# EndStops.net
KiCad netlist of a schematic drawn in Altium Designer
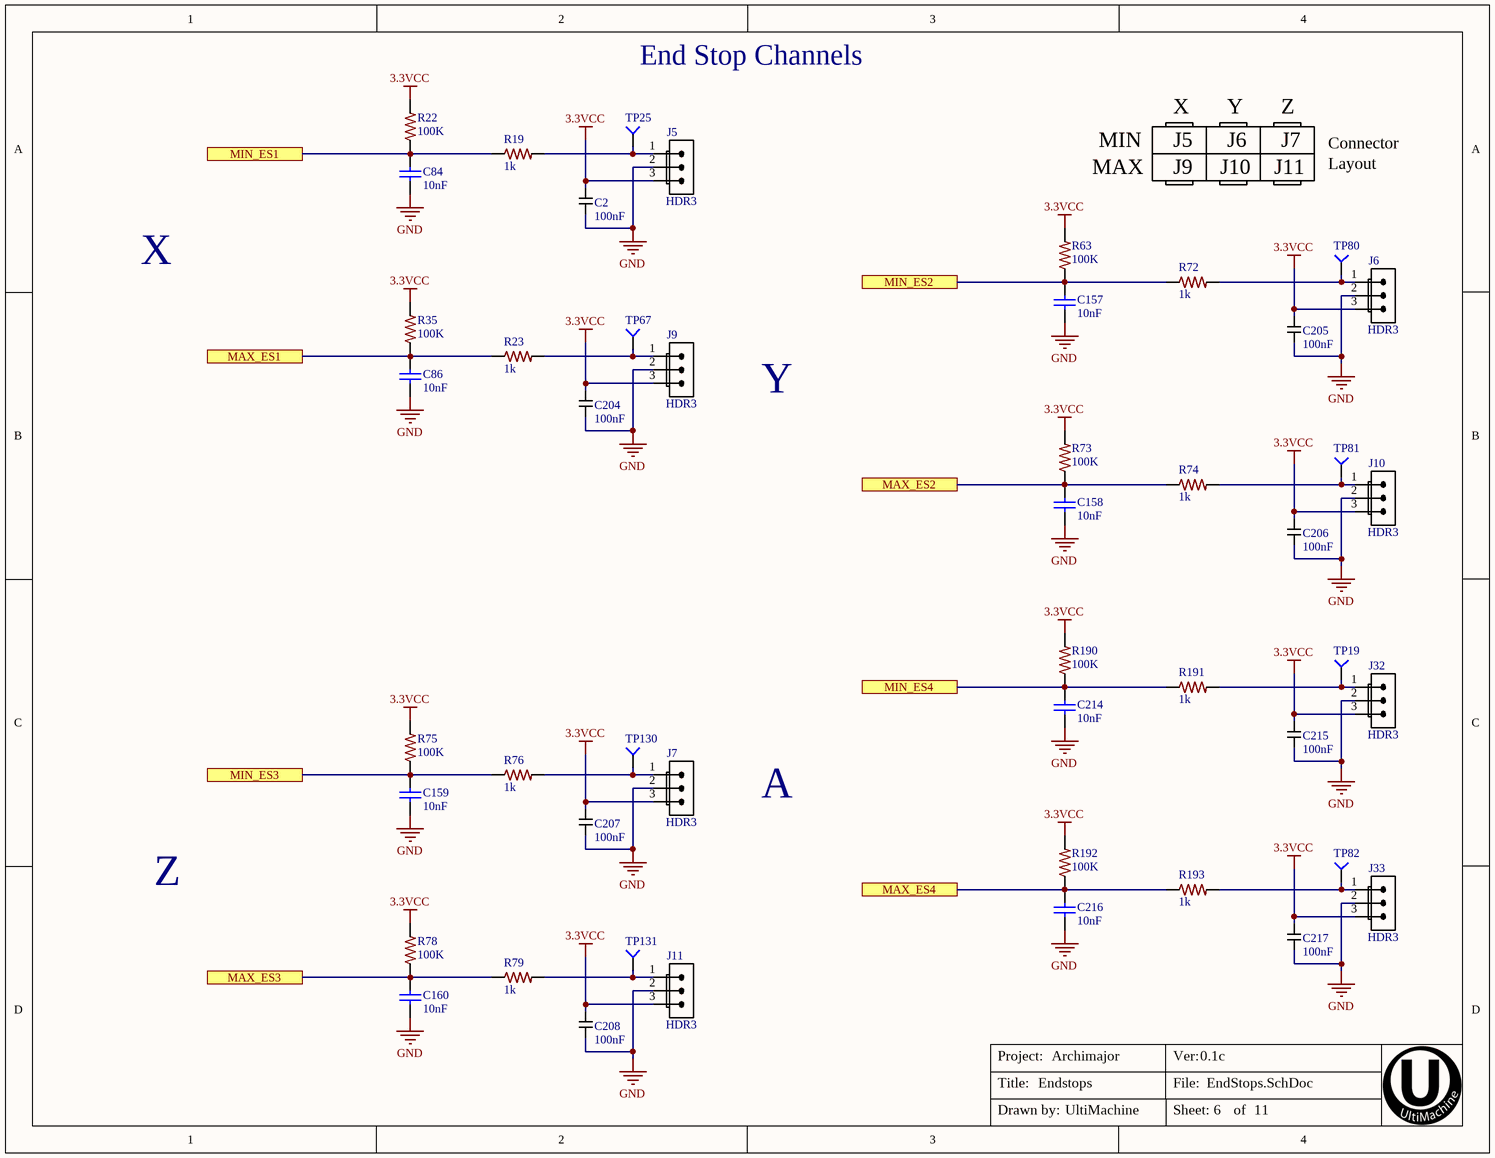
[diagram p0: EndStops.SchDoc]

(export (version "E")
  (design (tool "Eeschema 10.0.6"))
  (components
    (comp (ref "C2")
      (value "100nF")
      (footprint "C0201 Large Pads")
      (description "CAP CER 0.1UF 6.3V 10% X5R 0201")
      (fields (field (name "PART") "CL03A104KQ3NNNC") (field (name "MANUFACTURER") "Samsung"))
      (libsource (lib "Capacitors") (part "100nF 6.3V X5R 0201"))
    )
    (comp (ref "C84")
      (value "10nF")
      (footprint "C0402")
      (description "CAP CER 10nF 50V X7R 0402")
      (fields (field (name "TOLERANCE") "5%") (field (name "MANUFACTURER") "Murata"))
      (libsource (lib "Tigershark3D") (part "GRM155R71H103JA88D"))
    )
    (comp (ref "C86")
      (value "10nF")
      (footprint "C0402")
      (description "CAP CER 10nF 50V X7R 0402")
      (fields (field (name "TOLERANCE") "5%") (field (name "MANUFACTURER") "Murata"))
      (libsource (lib "Tigershark3D") (part "GRM155R71H103JA88D"))
    )
    (comp (ref "C157")
      (value "10nF")
      (footprint "C0402")
      (description "CAP CER 10nF 50V X7R 0402")
      (fields (field (name "TOLERANCE") "5%") (field (name "MANUFACTURER") "Murata"))
      (libsource (lib "Tigershark3D") (part "GRM155R71H103JA88D"))
    )
    (comp (ref "C158")
      (value "10nF")
      (footprint "C0402")
      (description "CAP CER 10nF 50V X7R 0402")
      (fields (field (name "TOLERANCE") "5%") (field (name "MANUFACTURER") "Murata"))
      (libsource (lib "Tigershark3D") (part "GRM155R71H103JA88D"))
    )
    (comp (ref "C159")
      (value "10nF")
      (footprint "C0402")
      (description "CAP CER 10nF 50V X7R 0402")
      (fields (field (name "TOLERANCE") "5%") (field (name "MANUFACTURER") "Murata"))
      (libsource (lib "Tigershark3D") (part "GRM155R71H103JA88D"))
    )
    (comp (ref "C160")
      (value "10nF")
      (footprint "C0402")
      (description "CAP CER 10nF 50V X7R 0402")
      (fields (field (name "TOLERANCE") "5%") (field (name "MANUFACTURER") "Murata"))
      (libsource (lib "Tigershark3D") (part "GRM155R71H103JA88D"))
    )
    (comp (ref "C204")
      (value "100nF")
      (footprint "C0201 Large Pads")
      (description "CAP CER 0.1UF 6.3V 10% X5R 0201")
      (fields (field (name "PART") "CL03A104KQ3NNNC") (field (name "MANUFACTURER") "Samsung"))
      (libsource (lib "Capacitors") (part "100nF 6.3V X5R 0201"))
    )
    (comp (ref "C205")
      (value "100nF")
      (footprint "C0201 Large Pads")
      (description "CAP CER 0.1UF 6.3V 10% X5R 0201")
      (fields (field (name "PART") "CL03A104KQ3NNNC") (field (name "MANUFACTURER") "Samsung"))
      (libsource (lib "Capacitors") (part "100nF 6.3V X5R 0201"))
    )
    (comp (ref "C206")
      (value "100nF")
      (footprint "C0201 Large Pads")
      (description "CAP CER 0.1UF 6.3V 10% X5R 0201")
      (fields (field (name "PART") "CL03A104KQ3NNNC") (field (name "MANUFACTURER") "Samsung"))
      (libsource (lib "Capacitors") (part "100nF 6.3V X5R 0201"))
    )
    (comp (ref "C207")
      (value "100nF")
      (footprint "C0201 Large Pads")
      (description "CAP CER 0.1UF 6.3V 10% X5R 0201")
      (fields (field (name "PART") "CL03A104KQ3NNNC") (field (name "MANUFACTURER") "Samsung"))
      (libsource (lib "Capacitors") (part "100nF 6.3V X5R 0201"))
    )
    (comp (ref "C208")
      (value "100nF")
      (footprint "C0201 Large Pads")
      (description "CAP CER 0.1UF 6.3V 10% X5R 0201")
      (fields (field (name "PART") "CL03A104KQ3NNNC") (field (name "MANUFACTURER") "Samsung"))
      (libsource (lib "Capacitors") (part "100nF 6.3V X5R 0201"))
    )
    (comp (ref "C214")
      (value "10nF")
      (footprint "C0402")
      (description "CAP CER 10nF 50V X7R 0402")
      (fields (field (name "TOLERANCE") "5%") (field (name "MANUFACTURER") "Murata"))
      (libsource (lib "Tigershark3D") (part "GRM155R71H103JA88D"))
    )
    (comp (ref "C215")
      (value "100nF")
      (footprint "C0201 Large Pads")
      (description "CAP CER 0.1UF 6.3V 10% X5R 0201")
      (fields (field (name "PART") "CL03A104KQ3NNNC") (field (name "MANUFACTURER") "Samsung"))
      (libsource (lib "Capacitors") (part "100nF 6.3V X5R 0201"))
    )
    (comp (ref "C216")
      (value "10nF")
      (footprint "C0402")
      (description "CAP CER 10nF 50V X7R 0402")
      (fields (field (name "TOLERANCE") "5%") (field (name "MANUFACTURER") "Murata"))
      (libsource (lib "Tigershark3D") (part "GRM155R71H103JA88D"))
    )
    (comp (ref "C217")
      (value "100nF")
      (footprint "C0201 Large Pads")
      (description "CAP CER 0.1UF 6.3V 10% X5R 0201")
      (fields (field (name "PART") "CL03A104KQ3NNNC") (field (name "MANUFACTURER") "Samsung"))
      (libsource (lib "Capacitors") (part "100nF 6.3V X5R 0201"))
    )
    (comp (ref "J5")
      (value "HDR3")
      (footprint "70543-02 PIN-IN-PASTE")
      (description "3 Positions Header, Shrouded Connector 0.100\" (2.54mm) Through Hole Gold - Pin in Paste")
      (fields (field (name "MANUFACTURER") "Molex") (field (name "PART") "0705430002"))
      (libsource (lib "Connectors") (part "CONN 3POS VERT 0.1{dblquote} SHRD LOCKING PIP"))
    )
    (comp (ref "J6")
      (value "HDR3")
      (footprint "70543-02 PIN-IN-PASTE")
      (description "3 Positions Header, Shrouded Connector 0.100\" (2.54mm) Through Hole Gold - Pin in Paste")
      (fields (field (name "MANUFACTURER") "Molex") (field (name "PART") "0705430002"))
      (libsource (lib "Connectors") (part "CONN 3POS VERT 0.1{dblquote} SHRD LOCKING PIP"))
    )
    (comp (ref "J7")
      (value "HDR3")
      (footprint "70543-02 PIN-IN-PASTE")
      (description "3 Positions Header, Shrouded Connector 0.100\" (2.54mm) Through Hole Gold - Pin in Paste")
      (fields (field (name "MANUFACTURER") "Molex") (field (name "PART") "0705430002"))
      (libsource (lib "Connectors") (part "CONN 3POS VERT 0.1{dblquote} SHRD LOCKING PIP"))
    )
    (comp (ref "J9")
      (value "HDR3")
      (footprint "70543-02 PIN-IN-PASTE")
      (description "3 Positions Header, Shrouded Connector 0.100\" (2.54mm) Through Hole Gold - Pin in Paste")
      (fields (field (name "MANUFACTURER") "Molex") (field (name "PART") "0705430002"))
      (libsource (lib "Connectors") (part "CONN 3POS VERT 0.1{dblquote} SHRD LOCKING PIP"))
    )
    (comp (ref "J10")
      (value "HDR3")
      (footprint "70543-02 PIN-IN-PASTE")
      (description "3 Positions Header, Shrouded Connector 0.100\" (2.54mm) Through Hole Gold - Pin in Paste")
      (fields (field (name "MANUFACTURER") "Molex") (field (name "PART") "0705430002"))
      (libsource (lib "Connectors") (part "CONN 3POS VERT 0.1{dblquote} SHRD LOCKING PIP"))
    )
    (comp (ref "J11")
      (value "HDR3")
      (footprint "70543-02 PIN-IN-PASTE")
      (description "3 Positions Header, Shrouded Connector 0.100\" (2.54mm) Through Hole Gold - Pin in Paste")
      (fields (field (name "MANUFACTURER") "Molex") (field (name "PART") "0705430002"))
      (libsource (lib "Connectors") (part "CONN 3POS VERT 0.1{dblquote} SHRD LOCKING PIP"))
    )
    (comp (ref "J32")
      (value "HDR3")
      (footprint "70543-02 PIN-IN-PASTE")
      (description "3 Positions Header, Shrouded Connector 0.100\" (2.54mm) Through Hole Gold - Pin in Paste")
      (fields (field (name "MANUFACTURER") "Molex") (field (name "PART") "0705430002"))
      (libsource (lib "Connectors") (part "CONN 3POS VERT 0.1{dblquote} SHRD LOCKING PIP"))
    )
    (comp (ref "J33")
      (value "HDR3")
      (footprint "70543-02 PIN-IN-PASTE")
      (description "3 Positions Header, Shrouded Connector 0.100\" (2.54mm) Through Hole Gold - Pin in Paste")
      (fields (field (name "MANUFACTURER") "Molex") (field (name "PART") "0705430002"))
      (libsource (lib "Connectors") (part "CONN 3POS VERT 0.1{dblquote} SHRD LOCKING PIP"))
    )
    (comp (ref "R19")
      (value "1k")
      (footprint "R0402")
      (description "RES 0402 1k 63mW 1%")
      (fields (field (name "MANUFACTURER") "Yageo") (field (name "PART") "RC0402FR-071KL"))
      (libsource (lib "3Delight") (part "RK73H1ETTP1001F"))
    )
    (comp (ref "R22")
      (value "100K")
      (footprint "R0402")
      (description "RES SMD 100K OHM 1% 1/16W 0402")
      (fields (field (name "MANUFACTURER") "Samsung") (field (name "PART") "RC1005F104CS"))
      (libsource (lib "Tigershark3D") (part "RC1005F104CS"))
    )
    (comp (ref "R23")
      (value "1k")
      (footprint "R0402")
      (description "RES 0402 1k 63mW 1%")
      (fields (field (name "MANUFACTURER") "Yageo") (field (name "PART") "RC0402FR-071KL"))
      (libsource (lib "3Delight") (part "RK73H1ETTP1001F"))
    )
    (comp (ref "R35")
      (value "100K")
      (footprint "R0402")
      (description "RES SMD 100K OHM 1% 1/16W 0402")
      (fields (field (name "MANUFACTURER") "Samsung") (field (name "PART") "RC1005F104CS"))
      (libsource (lib "Tigershark3D") (part "RC1005F104CS"))
    )
    (comp (ref "R63")
      (value "100K")
      (footprint "R0402")
      (description "RES SMD 100K OHM 1% 1/16W 0402")
      (fields (field (name "MANUFACTURER") "Samsung") (field (name "PART") "RC1005F104CS"))
      (libsource (lib "Tigershark3D") (part "RC1005F104CS"))
    )
    (comp (ref "R72")
      (value "1k")
      (footprint "R0402")
      (description "RES 0402 1k 63mW 1%")
      (fields (field (name "MANUFACTURER") "Yageo") (field (name "PART") "RC0402FR-071KL"))
      (libsource (lib "3Delight") (part "RK73H1ETTP1001F"))
    )
    (comp (ref "R73")
      (value "100K")
      (footprint "R0402")
      (description "RES SMD 100K OHM 1% 1/16W 0402")
      (fields (field (name "MANUFACTURER") "Samsung") (field (name "PART") "RC1005F104CS"))
      (libsource (lib "Tigershark3D") (part "RC1005F104CS"))
    )
    (comp (ref "R74")
      (value "1k")
      (footprint "R0402")
      (description "RES 0402 1k 63mW 1%")
      (fields (field (name "MANUFACTURER") "Yageo") (field (name "PART") "RC0402FR-071KL"))
      (libsource (lib "3Delight") (part "RK73H1ETTP1001F"))
    )
    (comp (ref "R75")
      (value "100K")
      (footprint "R0402")
      (description "RES SMD 100K OHM 1% 1/16W 0402")
      (fields (field (name "MANUFACTURER") "Samsung") (field (name "PART") "RC1005F104CS"))
      (libsource (lib "Tigershark3D") (part "RC1005F104CS"))
    )
    (comp (ref "R76")
      (value "1k")
      (footprint "R0402")
      (description "RES 0402 1k 63mW 1%")
      (fields (field (name "MANUFACTURER") "Yageo") (field (name "PART") "RC0402FR-071KL"))
      (libsource (lib "3Delight") (part "RK73H1ETTP1001F"))
    )
    (comp (ref "R78")
      (value "100K")
      (footprint "R0402")
      (description "RES SMD 100K OHM 1% 1/16W 0402")
      (fields (field (name "MANUFACTURER") "Samsung") (field (name "PART") "RC1005F104CS"))
      (libsource (lib "Tigershark3D") (part "RC1005F104CS"))
    )
    (comp (ref "R79")
      (value "1k")
      (footprint "R0402")
      (description "RES 0402 1k 63mW 1%")
      (fields (field (name "MANUFACTURER") "Yageo") (field (name "PART") "RC0402FR-071KL"))
      (libsource (lib "3Delight") (part "RK73H1ETTP1001F"))
    )
    (comp (ref "R190")
      (value "100K")
      (footprint "R0402")
      (description "RES SMD 100K OHM 1% 1/16W 0402")
      (fields (field (name "MANUFACTURER") "Samsung") (field (name "PART") "RC1005F104CS"))
      (libsource (lib "Tigershark3D") (part "RC1005F104CS"))
    )
    (comp (ref "R191")
      (value "1k")
      (footprint "R0402")
      (description "RES 0402 1k 63mW 1%")
      (fields (field (name "MANUFACTURER") "Yageo") (field (name "PART") "RC0402FR-071KL"))
      (libsource (lib "3Delight") (part "RK73H1ETTP1001F"))
    )
    (comp (ref "R192")
      (value "100K")
      (footprint "R0402")
      (description "RES SMD 100K OHM 1% 1/16W 0402")
      (fields (field (name "MANUFACTURER") "Samsung") (field (name "PART") "RC1005F104CS"))
      (libsource (lib "Tigershark3D") (part "RC1005F104CS"))
    )
    (comp (ref "R193")
      (value "1k")
      (footprint "R0402")
      (description "RES 0402 1k 63mW 1%")
      (fields (field (name "MANUFACTURER") "Yageo") (field (name "PART") "RC0402FR-071KL"))
      (libsource (lib "3Delight") (part "RK73H1ETTP1001F"))
    )
    (comp (ref "TP19")
      (value "TP4")
      (footprint "TP-2")
      (description "Socket")
      (fields (field (name "PART") "NOTAPART-Testpoint"))
      (libsource (lib "Archim") (part "Socket"))
    )
    (comp (ref "TP25")
      (value "TP4")
      (footprint "TP-2")
      (description "Socket")
      (fields (field (name "PART") "NOTAPART-Testpoint"))
      (libsource (lib "Archim") (part "Socket"))
    )
    (comp (ref "TP67")
      (value "TP4")
      (footprint "TP-2")
      (description "Socket")
      (fields (field (name "PART") "NOTAPART-Testpoint"))
      (libsource (lib "Archim") (part "Socket"))
    )
    (comp (ref "TP80")
      (value "TP4")
      (footprint "TP-2")
      (description "Socket")
      (fields (field (name "PART") "NOTAPART-Testpoint"))
      (libsource (lib "Archim") (part "Socket"))
    )
    (comp (ref "TP81")
      (value "TP4")
      (footprint "TP-2")
      (description "Socket")
      (fields (field (name "PART") "NOTAPART-Testpoint"))
      (libsource (lib "Archim") (part "Socket"))
    )
    (comp (ref "TP82")
      (value "TP4")
      (footprint "TP-2")
      (description "Socket")
      (fields (field (name "PART") "NOTAPART-Testpoint"))
      (libsource (lib "Archim") (part "Socket"))
    )
    (comp (ref "TP130")
      (value "TP4")
      (footprint "TP-2")
      (description "Socket")
      (fields (field (name "PART") "NOTAPART-Testpoint"))
      (libsource (lib "Archim") (part "Socket"))
    )
    (comp (ref "TP131")
      (value "TP4")
      (footprint "TP-2")
      (description "Socket")
      (fields (field (name "PART") "NOTAPART-Testpoint"))
      (libsource (lib "Archim") (part "Socket"))
    )
  )
  (nets
    (net (code "1") (name "/MAX_ES1") (class "Default")
      (node (ref "C86") (pin "1") (pinfunction "1_1") (pintype "passive"))
      (node (ref "R23") (pin "1") (pinfunction "1_1") (pintype "passive"))
      (node (ref "R35") (pin "1") (pinfunction "1_1") (pintype "passive"))
    )
    (net (code "2") (name "/MAX_ES2") (class "Default")
      (node (ref "C158") (pin "1") (pinfunction "1_1") (pintype "passive"))
      (node (ref "R73") (pin "1") (pinfunction "1_1") (pintype "passive"))
      (node (ref "R74") (pin "1") (pinfunction "1_1") (pintype "passive"))
    )
    (net (code "3") (name "/MAX_ES3") (class "Default")
      (node (ref "C160") (pin "1") (pinfunction "1_1") (pintype "passive"))
      (node (ref "R78") (pin "1") (pinfunction "1_1") (pintype "passive"))
      (node (ref "R79") (pin "1") (pinfunction "1_1") (pintype "passive"))
    )
    (net (code "4") (name "/MAX_ES4") (class "Default")
      (node (ref "C216") (pin "1") (pinfunction "1_1") (pintype "passive"))
      (node (ref "R192") (pin "1") (pinfunction "1_1") (pintype "passive"))
      (node (ref "R193") (pin "1") (pinfunction "1_1") (pintype "passive"))
    )
    (net (code "5") (name "/MIN_ES1") (class "Default")
      (node (ref "C84") (pin "1") (pinfunction "1_1") (pintype "passive"))
      (node (ref "R19") (pin "1") (pinfunction "1_1") (pintype "passive"))
      (node (ref "R22") (pin "1") (pinfunction "1_1") (pintype "passive"))
    )
    (net (code "6") (name "/MIN_ES2") (class "Default")
      (node (ref "C157") (pin "1") (pinfunction "1_1") (pintype "passive"))
      (node (ref "R63") (pin "1") (pinfunction "1_1") (pintype "passive"))
      (node (ref "R72") (pin "1") (pinfunction "1_1") (pintype "passive"))
    )
    (net (code "7") (name "/MIN_ES3") (class "Default")
      (node (ref "C159") (pin "1") (pinfunction "1_1") (pintype "passive"))
      (node (ref "R75") (pin "1") (pinfunction "1_1") (pintype "passive"))
      (node (ref "R76") (pin "1") (pinfunction "1_1") (pintype "passive"))
    )
    (net (code "8") (name "/MIN_ES4") (class "Default")
      (node (ref "C214") (pin "1") (pinfunction "1_1") (pintype "passive"))
      (node (ref "R190") (pin "1") (pinfunction "1_1") (pintype "passive"))
      (node (ref "R191") (pin "1") (pinfunction "1_1") (pintype "passive"))
    )
    (net (code "9") (name "3.3VCC") (class "Default")
      (node (ref "C2") (pin "2") (pinfunction "2_2") (pintype "passive"))
      (node (ref "C204") (pin "2") (pinfunction "2_2") (pintype "passive"))
      (node (ref "C205") (pin "2") (pinfunction "2_2") (pintype "passive"))
      (node (ref "C206") (pin "2") (pinfunction "2_2") (pintype "passive"))
      (node (ref "C207") (pin "2") (pinfunction "2_2") (pintype "passive"))
      (node (ref "C208") (pin "2") (pinfunction "2_2") (pintype "passive"))
      (node (ref "C215") (pin "2") (pinfunction "2_2") (pintype "passive"))
      (node (ref "C217") (pin "2") (pinfunction "2_2") (pintype "passive"))
      (node (ref "J10") (pin "3") (pinfunction "S_3") (pintype "passive"))
      (node (ref "J11") (pin "3") (pinfunction "S_3") (pintype "passive"))
      (node (ref "J32") (pin "3") (pinfunction "S_3") (pintype "passive"))
      (node (ref "J33") (pin "3") (pinfunction "S_3") (pintype "passive"))
      (node (ref "J5") (pin "3") (pinfunction "S_3") (pintype "passive"))
      (node (ref "J6") (pin "3") (pinfunction "S_3") (pintype "passive"))
      (node (ref "J7") (pin "3") (pinfunction "S_3") (pintype "passive"))
      (node (ref "J9") (pin "3") (pinfunction "S_3") (pintype "passive"))
      (node (ref "R190") (pin "2") (pinfunction "2_2") (pintype "passive"))
      (node (ref "R192") (pin "2") (pinfunction "2_2") (pintype "passive"))
      (node (ref "R22") (pin "2") (pinfunction "2_2") (pintype "passive"))
      (node (ref "R35") (pin "2") (pinfunction "2_2") (pintype "passive"))
      (node (ref "R63") (pin "2") (pinfunction "2_2") (pintype "passive"))
      (node (ref "R73") (pin "2") (pinfunction "2_2") (pintype "passive"))
      (node (ref "R75") (pin "2") (pinfunction "2_2") (pintype "passive"))
      (node (ref "R78") (pin "2") (pinfunction "2_2") (pintype "passive"))
    )
    (net (code "10") (name "GND") (class "Default")
      (node (ref "C157") (pin "2") (pinfunction "2_2") (pintype "passive"))
      (node (ref "C158") (pin "2") (pinfunction "2_2") (pintype "passive"))
      (node (ref "C159") (pin "2") (pinfunction "2_2") (pintype "passive"))
      (node (ref "C160") (pin "2") (pinfunction "2_2") (pintype "passive"))
      (node (ref "C2") (pin "1") (pinfunction "1_1") (pintype "passive"))
      (node (ref "C204") (pin "1") (pinfunction "1_1") (pintype "passive"))
      (node (ref "C205") (pin "1") (pinfunction "1_1") (pintype "passive"))
      (node (ref "C206") (pin "1") (pinfunction "1_1") (pintype "passive"))
      (node (ref "C207") (pin "1") (pinfunction "1_1") (pintype "passive"))
      (node (ref "C208") (pin "1") (pinfunction "1_1") (pintype "passive"))
      (node (ref "C214") (pin "2") (pinfunction "2_2") (pintype "passive"))
      (node (ref "C215") (pin "1") (pinfunction "1_1") (pintype "passive"))
      (node (ref "C216") (pin "2") (pinfunction "2_2") (pintype "passive"))
      (node (ref "C217") (pin "1") (pinfunction "1_1") (pintype "passive"))
      (node (ref "C84") (pin "2") (pinfunction "2_2") (pintype "passive"))
      (node (ref "C86") (pin "2") (pinfunction "2_2") (pintype "passive"))
      (node (ref "J10") (pin "2") (pinfunction "S_2") (pintype "passive"))
      (node (ref "J11") (pin "2") (pinfunction "S_2") (pintype "passive"))
      (node (ref "J32") (pin "2") (pinfunction "S_2") (pintype "passive"))
      (node (ref "J33") (pin "2") (pinfunction "S_2") (pintype "passive"))
      (node (ref "J5") (pin "2") (pinfunction "S_2") (pintype "passive"))
      (node (ref "J6") (pin "2") (pinfunction "S_2") (pintype "passive"))
      (node (ref "J7") (pin "2") (pinfunction "S_2") (pintype "passive"))
      (node (ref "J9") (pin "2") (pinfunction "S_2") (pintype "passive"))
    )
    (net (code "11") (name "Net-(J5-S-Pad1)") (class "Default")
      (node (ref "J5") (pin "1") (pinfunction "S_1") (pintype "passive"))
      (node (ref "R19") (pin "2") (pinfunction "2_2") (pintype "passive"))
      (node (ref "TP25") (pin "1") (pinfunction "1_1") (pintype "passive"))
    )
    (net (code "12") (name "Net-(J6-S-Pad1)") (class "Default")
      (node (ref "J6") (pin "1") (pinfunction "S_1") (pintype "passive"))
      (node (ref "R72") (pin "2") (pinfunction "2_2") (pintype "passive"))
      (node (ref "TP80") (pin "1") (pinfunction "1_1") (pintype "passive"))
    )
    (net (code "13") (name "Net-(J7-S-Pad1)") (class "Default")
      (node (ref "J7") (pin "1") (pinfunction "S_1") (pintype "passive"))
      (node (ref "R76") (pin "2") (pinfunction "2_2") (pintype "passive"))
      (node (ref "TP130") (pin "1") (pinfunction "1_1") (pintype "passive"))
    )
    (net (code "14") (name "Net-(J9-S-Pad1)") (class "Default")
      (node (ref "J9") (pin "1") (pinfunction "S_1") (pintype "passive"))
      (node (ref "R23") (pin "2") (pinfunction "2_2") (pintype "passive"))
      (node (ref "TP67") (pin "1") (pinfunction "1_1") (pintype "passive"))
    )
    (net (code "15") (name "Net-(J10-S-Pad1)") (class "Default")
      (node (ref "J10") (pin "1") (pinfunction "S_1") (pintype "passive"))
      (node (ref "R74") (pin "2") (pinfunction "2_2") (pintype "passive"))
      (node (ref "TP81") (pin "1") (pinfunction "1_1") (pintype "passive"))
    )
    (net (code "16") (name "Net-(J11-S-Pad1)") (class "Default")
      (node (ref "J11") (pin "1") (pinfunction "S_1") (pintype "passive"))
      (node (ref "R79") (pin "2") (pinfunction "2_2") (pintype "passive"))
      (node (ref "TP131") (pin "1") (pinfunction "1_1") (pintype "passive"))
    )
    (net (code "17") (name "Net-(J32-S-Pad1)") (class "Default")
      (node (ref "J32") (pin "1") (pinfunction "S_1") (pintype "passive"))
      (node (ref "R191") (pin "2") (pinfunction "2_2") (pintype "passive"))
      (node (ref "TP19") (pin "1") (pinfunction "1_1") (pintype "passive"))
    )
    (net (code "18") (name "Net-(J33-S-Pad1)") (class "Default")
      (node (ref "J33") (pin "1") (pinfunction "S_1") (pintype "passive"))
      (node (ref "R193") (pin "2") (pinfunction "2_2") (pintype "passive"))
      (node (ref "TP82") (pin "1") (pinfunction "1_1") (pintype "passive"))
    )
  )
)
